# Driver.net
KiCad netlist of a schematic drawn in EAGLE
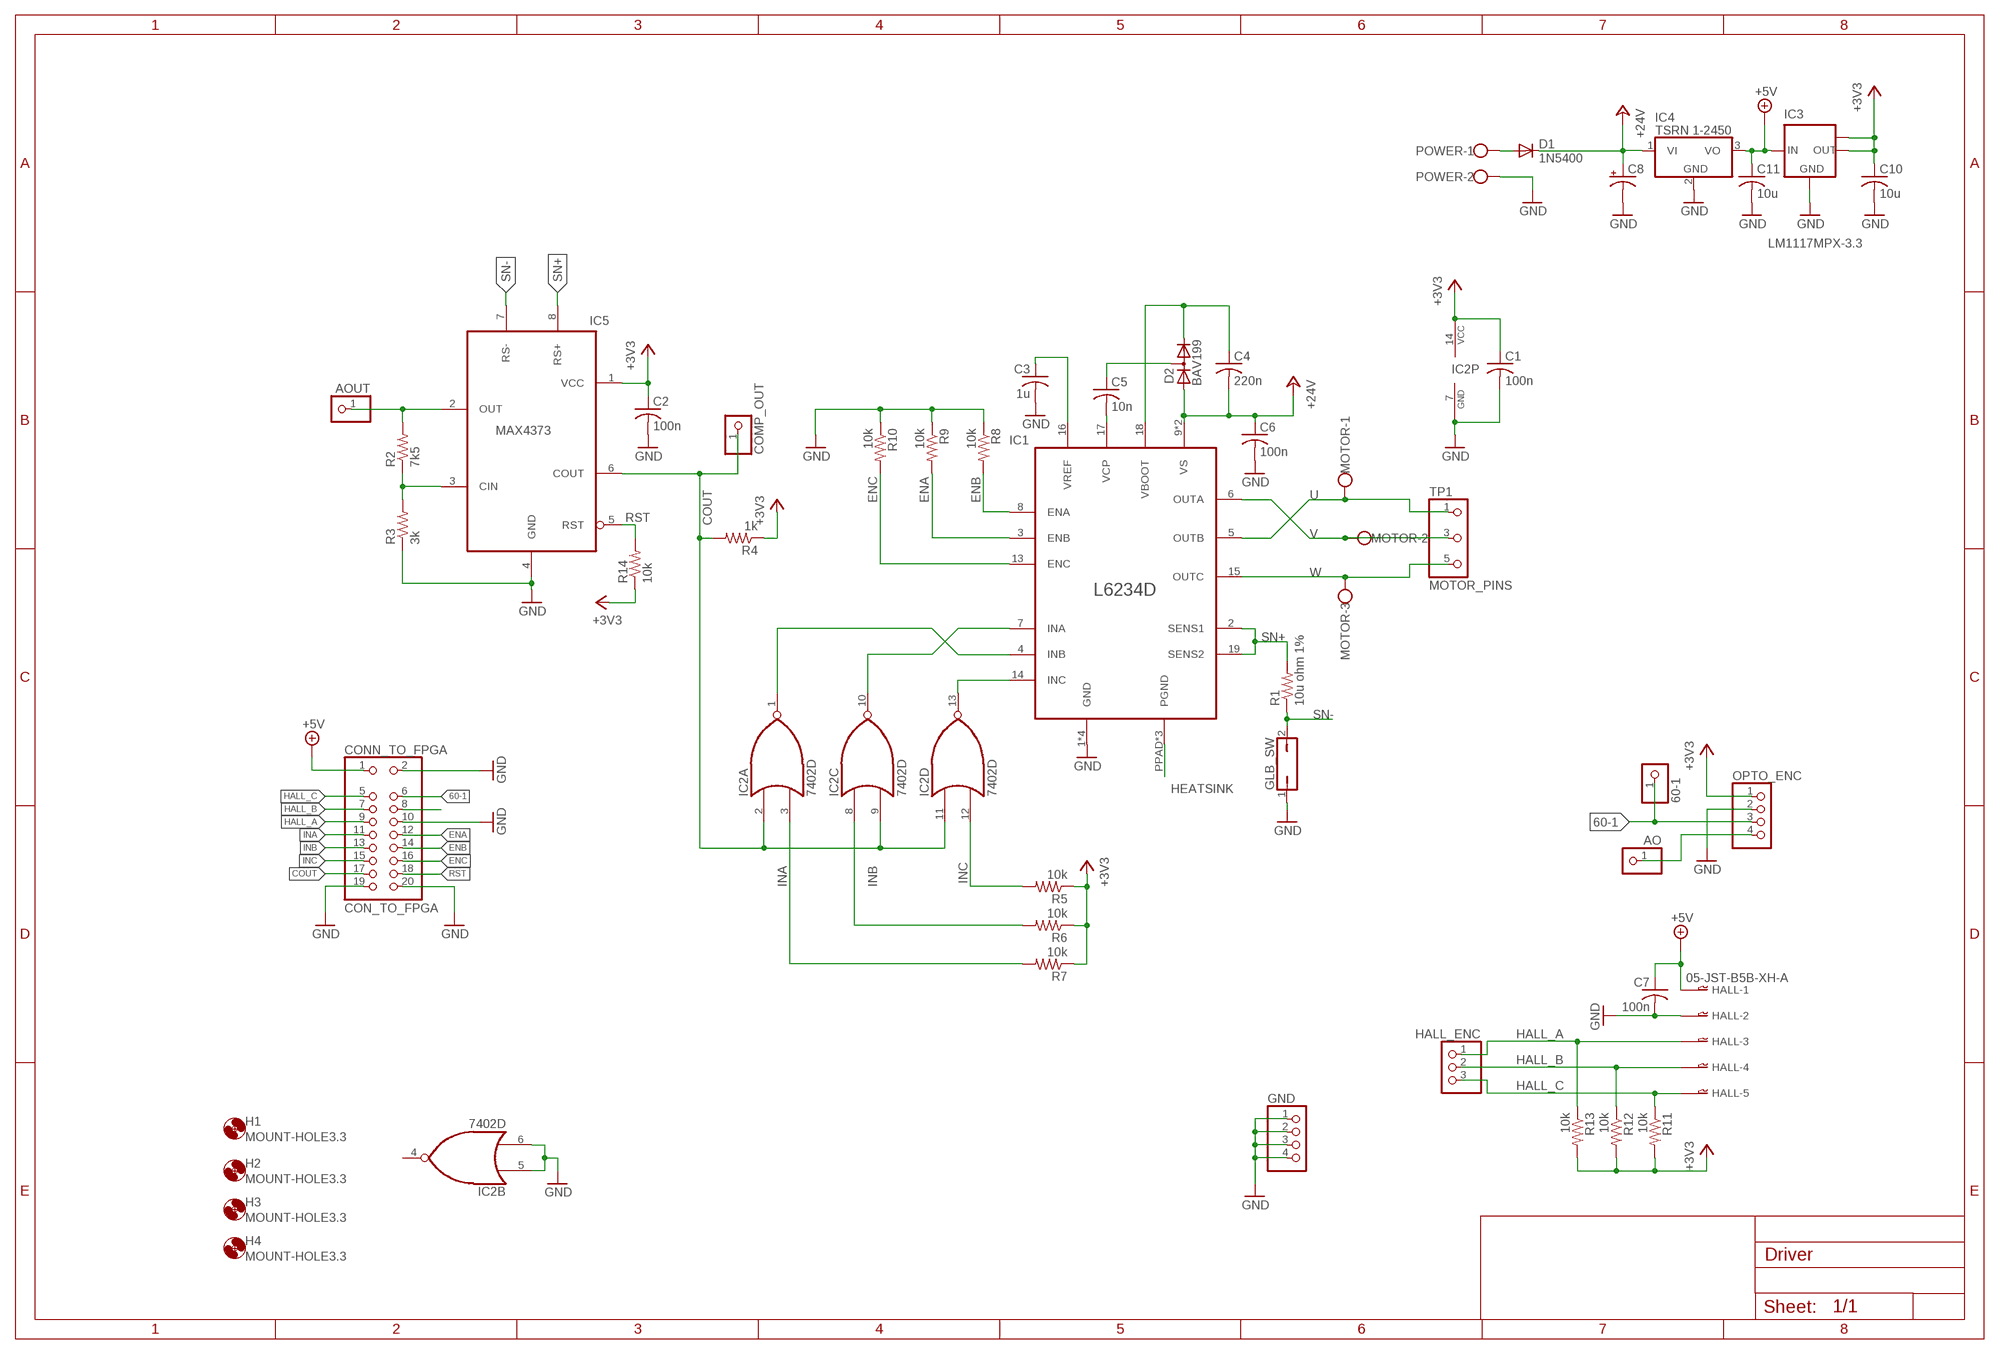
[diagram p0: schematic, sheet 1]

(export (version "E")
  (design (tool "Eeschema 10.0.6"))
  (components
    (comp (ref "60-1")
      (value "PINHD-1X1")
      (footprint "eagle-import:1X01")
      (libsource (lib "eagle-import") (part "PINHD-1X1"))
    )
    (comp (ref "AO")
      (value "PINHD-1X1")
      (footprint "eagle-import:1X01")
      (libsource (lib "eagle-import") (part "PINHD-1X1"))
    )
    (comp (ref "AOUT")
      (value "PINHD-1X1")
      (footprint "eagle-import:1X01")
      (libsource (lib "eagle-import") (part "PINHD-1X1"))
    )
    (comp (ref "C1")
      (value "100n")
      (footprint "eagle-import:C0805")
      (libsource (lib "eagle-import") (part "C-USC0805"))
    )
    (comp (ref "C2")
      (value "100n")
      (footprint "eagle-import:C0805")
      (libsource (lib "eagle-import") (part "C-USC0805"))
    )
    (comp (ref "C3")
      (value "1u")
      (footprint "eagle-import:C0805")
      (libsource (lib "eagle-import") (part "C-USC0805"))
    )
    (comp (ref "C4")
      (value "220n")
      (footprint "eagle-import:C0805")
      (libsource (lib "eagle-import") (part "C-USC0805"))
    )
    (comp (ref "C5")
      (value "10n")
      (footprint "eagle-import:C0805")
      (libsource (lib "eagle-import") (part "C-USC0805"))
    )
    (comp (ref "C6")
      (value "100n")
      (footprint "eagle-import:C0805")
      (libsource (lib "eagle-import") (part "C-USC0805"))
    )
    (comp (ref "C7")
      (value "100n")
      (footprint "eagle-import:C0805")
      (libsource (lib "eagle-import") (part "C-USC0805"))
    )
    (comp (ref "C8")
      (value "CPOL-USE5-13")
      (footprint "eagle-import:E5-13")
      (libsource (lib "eagle-import") (part "CPOL-USE5-13"))
    )
    (comp (ref "C10")
      (value "10u")
      (footprint "eagle-import:C1206K")
      (libsource (lib "eagle-import") (part "C-USC1206K"))
    )
    (comp (ref "C11")
      (value "10u")
      (footprint "eagle-import:C1206K")
      (libsource (lib "eagle-import") (part "C-USC1206K"))
    )
    (comp (ref "COMP_OUT")
      (value "PINHD-1X1")
      (footprint "eagle-import:1X01")
      (libsource (lib "eagle-import") (part "PINHD-1X1"))
    )
    (comp (ref "CONN_TO_FPGA")
      (value "CON_TO_FPGA")
      (footprint "eagle-import:2X10-2")
      (libsource (lib "eagle-import") (part "CON_TO_FPGA"))
    )
    (comp (ref "D1")
      (value "1N5400")
      (footprint "eagle-import:DO201-15")
      (libsource (lib "eagle-import") (part "1N5400"))
    )
    (comp (ref "D2")
      (value "BAV199")
      (footprint "eagle-import:SOT23")
      (libsource (lib "eagle-import") (part "BAV199"))
    )
    (comp (ref "GLB_SW")
      (value "JP1Q")
      (footprint "eagle-import:JP1")
      (libsource (lib "eagle-import") (part "JP1Q"))
    )
    (comp (ref "GND")
      (value "PINHD-1X4")
      (footprint "eagle-import:1X04")
      (libsource (lib "eagle-import") (part "PINHD-1X4"))
    )
    (comp (ref "H1")
      (value "MOUNT-HOLE3.3")
      (footprint "eagle-import:3,3")
      (libsource (lib "eagle-import") (part "MOUNT-HOLE3.3"))
    )
    (comp (ref "H2")
      (value "MOUNT-HOLE3.3")
      (footprint "eagle-import:3,3")
      (libsource (lib "eagle-import") (part "MOUNT-HOLE3.3"))
    )
    (comp (ref "H3")
      (value "MOUNT-HOLE3.3")
      (footprint "eagle-import:3,3")
      (libsource (lib "eagle-import") (part "MOUNT-HOLE3.3"))
    )
    (comp (ref "H4")
      (value "MOUNT-HOLE3.3")
      (footprint "eagle-import:3,3")
      (libsource (lib "eagle-import") (part "MOUNT-HOLE3.3"))
    )
    (comp (ref "HALL")
      (value "05-JST-B5B-XH-A")
      (footprint "eagle-import:B5B-XH")
      (libsource (lib "eagle-import") (part "05-JST-B5B-XH-A"))
    )
    (comp (ref "HALL_ENC")
      (value "PINHD-1X3")
      (footprint "eagle-import:1X03")
      (libsource (lib "eagle-import") (part "PINHD-1X3"))
    )
    (comp (ref "IC1")
      (value "L6234D")
      (footprint "eagle-import:POWER_SO20")
      (libsource (lib "eagle-import") (part "L6234D"))
    )
    (comp (ref "IC2")
      (value "7402D")
      (footprint "eagle-import:SO14")
      (libsource (lib "eagle-import") (part "7402D"))
    )
    (comp (ref "IC3")
      (value "LM1117MPX-3.3")
      (footprint "eagle-import:SOT223")
      (libsource (lib "eagle-import") (part "LM1117MPX-3.3"))
    )
    (comp (ref "IC4")
      (value "TSRN 1-2450")
      (footprint "eagle-import:TSRN-1")
      (libsource (lib "eagle-import") (part "REG"))
    )
    (comp (ref "IC5")
      (value "MAX4373")
      (footprint "eagle-import:SO-8")
      (libsource (lib "eagle-import") (part "MAX4373"))
    )
    (comp (ref "MOTOR")
      (value "W237-103")
      (footprint "eagle-import:W237-103")
      (fields (field (name "MPN") "237-103"))
      (libsource (lib "eagle-import") (part "W237-103"))
    )
    (comp (ref "OPTO_ENC")
      (value "PINHD-1X4")
      (footprint "eagle-import:1X04")
      (libsource (lib "eagle-import") (part "PINHD-1X4"))
    )
    (comp (ref "POWER")
      (value "W237-102")
      (footprint "eagle-import:W237-102")
      (fields (field (name "MPN") "237-102"))
      (libsource (lib "eagle-import") (part "W237-102"))
    )
    (comp (ref "R1")
      (value "10u ohm 1%")
      (footprint "eagle-import:R2512")
      (libsource (lib "eagle-import") (part "R-US_R2512"))
    )
    (comp (ref "R2")
      (value "7k5")
      (footprint "eagle-import:M1206")
      (libsource (lib "eagle-import") (part "R-US_M1206"))
    )
    (comp (ref "R3")
      (value "3k")
      (footprint "eagle-import:M1206")
      (libsource (lib "eagle-import") (part "R-US_M1206"))
    )
    (comp (ref "R4")
      (value "1k")
      (footprint "eagle-import:M1206")
      (libsource (lib "eagle-import") (part "R-US_M1206"))
    )
    (comp (ref "R5")
      (value "10k")
      (footprint "eagle-import:M1206")
      (libsource (lib "eagle-import") (part "R-US_M1206"))
    )
    (comp (ref "R6")
      (value "10k")
      (footprint "eagle-import:M1206")
      (libsource (lib "eagle-import") (part "R-US_M1206"))
    )
    (comp (ref "R7")
      (value "10k")
      (footprint "eagle-import:M1206")
      (libsource (lib "eagle-import") (part "R-US_M1206"))
    )
    (comp (ref "R8")
      (value "10k")
      (footprint "eagle-import:M1206")
      (libsource (lib "eagle-import") (part "R-US_M1206"))
    )
    (comp (ref "R9")
      (value "10k")
      (footprint "eagle-import:M1206")
      (libsource (lib "eagle-import") (part "R-US_M1206"))
    )
    (comp (ref "R10")
      (value "10k")
      (footprint "eagle-import:M1206")
      (libsource (lib "eagle-import") (part "R-US_M1206"))
    )
    (comp (ref "R11")
      (value "10k")
      (footprint "eagle-import:M1206")
      (libsource (lib "eagle-import") (part "R-US_M1206"))
    )
    (comp (ref "R12")
      (value "10k")
      (footprint "eagle-import:M1206")
      (libsource (lib "eagle-import") (part "R-US_M1206"))
    )
    (comp (ref "R13")
      (value "10k")
      (footprint "eagle-import:M1206")
      (libsource (lib "eagle-import") (part "R-US_M1206"))
    )
    (comp (ref "R14")
      (value "10k")
      (footprint "eagle-import:M1206")
      (libsource (lib "eagle-import") (part "R-US_M1206"))
    )
    (comp (ref "TP1")
      (value "MOTOR_PINS")
      (footprint "eagle-import:PINSX3-200")
      (libsource (lib "eagle-import") (part "MOTOR_PINS"))
    )
  )
  (nets
    (net (code "1") (name "+3V3") (class "Default")
      (node (ref "C1") (pin "1") (pinfunction "1_1") (pintype "passive"))
      (node (ref "C10") (pin "1") (pinfunction "1_1") (pintype "passive"))
      (node (ref "C2") (pin "1") (pinfunction "1_1") (pintype "passive"))
      (node (ref "IC2") (pin "14") (pinfunction "VCC_14") (pintype "power_in"))
      (node (ref "IC3") (pin "2") (pinfunction "OUT_2") (pintype "passive"))
      (node (ref "IC3") (pin "TAB") (pinfunction "OUT1_TAB") (pintype "passive"))
      (node (ref "IC5") (pin "1") (pinfunction "VCC_1") (pintype "power_in"))
      (node (ref "OPTO_ENC") (pin "1") (pinfunction "1_1") (pintype "passive"))
      (node (ref "R11") (pin "2") (pinfunction "2_2") (pintype "passive"))
      (node (ref "R12") (pin "2") (pinfunction "2_2") (pintype "passive"))
      (node (ref "R13") (pin "2") (pinfunction "2_2") (pintype "passive"))
      (node (ref "R14") (pin "1") (pinfunction "1_1") (pintype "passive"))
      (node (ref "R4") (pin "1") (pinfunction "1_1") (pintype "passive"))
      (node (ref "R5") (pin "1") (pinfunction "1_1") (pintype "passive"))
      (node (ref "R6") (pin "1") (pinfunction "1_1") (pintype "passive"))
      (node (ref "R7") (pin "1") (pinfunction "1_1") (pintype "passive"))
    )
    (net (code "2") (name "+5V") (class "Default")
      (node (ref "C11") (pin "1") (pinfunction "1_1") (pintype "passive"))
      (node (ref "C7") (pin "1") (pinfunction "1_1") (pintype "passive"))
      (node (ref "CONN_TO_FPGA") (pin "1") (pinfunction "1_1") (pintype "passive"))
      (node (ref "HALL") (pin "P$1") (pinfunction "1_P$1") (pintype "passive"))
      (node (ref "IC3") (pin "3") (pinfunction "IN_3") (pintype "input"))
      (node (ref "IC4") (pin "3") (pinfunction "VO_3") (pintype "passive"))
    )
    (net (code "3") (name "+24V") (class "Default")
      (node (ref "C4") (pin "2") (pinfunction "2_2") (pintype "passive"))
      (node (ref "C6") (pin "1") (pinfunction "1_1") (pintype "passive"))
      (node (ref "C8") (pin "+") (pinfunction "+_+") (pintype "passive"))
      (node (ref "D1") (pin "C") (pinfunction "C_C") (pintype "passive"))
      (node (ref "D2") (pin "1") (pinfunction "A_1") (pintype "passive"))
      (node (ref "IC1") (pin "12") (pinfunction "VS_12") (pintype "power_in"))
      (node (ref "IC1") (pin "9") (pinfunction "VS_9") (pintype "power_in"))
      (node (ref "IC4") (pin "1") (pinfunction "VI_1") (pintype "input"))
    )
    (net (code "4") (name "/HEATSINK") (class "Default")
      (node (ref "IC1") (pin "PPAD") (pinfunction "PGND_PPAD") (pintype "power_in"))
      (node (ref "IC1") (pin "PPAD1") (pinfunction "PGND_PPAD1") (pintype "power_in"))
      (node (ref "IC1") (pin "PPAD2") (pinfunction "PGND_PPAD2") (pintype "power_in"))
    )
    (net (code "5") (name "/U") (class "Default")
      (node (ref "IC1") (pin "5") (pinfunction "OUTB_5") (pintype "output"))
      (node (ref "MOTOR") (pin "1") (pinfunction "KL_1") (pintype "passive"))
      (node (ref "TP1") (pin "1") (pinfunction "1_1") (pintype "passive"))
    )
    (net (code "6") (name "/V") (class "Default")
      (node (ref "IC1") (pin "6") (pinfunction "OUTA_6") (pintype "output"))
      (node (ref "MOTOR") (pin "2") (pinfunction "KL_2") (pintype "passive"))
      (node (ref "TP1") (pin "3") (pinfunction "3_3") (pintype "passive"))
    )
    (net (code "7") (name "/W") (class "Default")
      (node (ref "IC1") (pin "15") (pinfunction "OUTC_15") (pintype "output"))
      (node (ref "MOTOR") (pin "3") (pinfunction "KL_3") (pintype "passive"))
      (node (ref "TP1") (pin "5") (pinfunction "5_5") (pintype "passive"))
    )
    (net (code "8") (name "60-1") (class "Default")
      (node (ref "60-1") (pin "1") (pinfunction "1_1") (pintype "passive"))
      (node (ref "CONN_TO_FPGA") (pin "6") (pinfunction "6_6") (pintype "passive"))
      (node (ref "OPTO_ENC") (pin "3") (pinfunction "3_3") (pintype "passive"))
    )
    (net (code "9") (name "COUT") (class "Default")
      (node (ref "COMP_OUT") (pin "1") (pinfunction "1_1") (pintype "passive"))
      (node (ref "CONN_TO_FPGA") (pin "17") (pinfunction "17_17") (pintype "passive"))
      (node (ref "IC2") (pin "11") (pinfunction "I0_11") (pintype "input"))
      (node (ref "IC2") (pin "2") (pinfunction "I0_2") (pintype "input"))
      (node (ref "IC2") (pin "9") (pinfunction "I1_9") (pintype "input"))
      (node (ref "IC5") (pin "6") (pinfunction "COUT_6") (pintype "output"))
      (node (ref "R4") (pin "2") (pinfunction "2_2") (pintype "passive"))
    )
    (net (code "10") (name "ENA") (class "Default")
      (node (ref "CONN_TO_FPGA") (pin "12") (pinfunction "12_12") (pintype "passive"))
      (node (ref "IC1") (pin "3") (pinfunction "ENB_3") (pintype "input"))
      (node (ref "R9") (pin "2") (pinfunction "2_2") (pintype "passive"))
    )
    (net (code "11") (name "ENB") (class "Default")
      (node (ref "CONN_TO_FPGA") (pin "14") (pinfunction "14_14") (pintype "passive"))
      (node (ref "IC1") (pin "8") (pinfunction "ENA_8") (pintype "input"))
      (node (ref "R8") (pin "2") (pinfunction "2_2") (pintype "passive"))
    )
    (net (code "12") (name "ENC") (class "Default")
      (node (ref "CONN_TO_FPGA") (pin "16") (pinfunction "16_16") (pintype "passive"))
      (node (ref "IC1") (pin "13") (pinfunction "ENC_13") (pintype "input"))
      (node (ref "R10") (pin "2") (pinfunction "2_2") (pintype "passive"))
    )
    (net (code "13") (name "GND") (class "Default")
      (node (ref "C1") (pin "2") (pinfunction "2_2") (pintype "passive"))
      (node (ref "C10") (pin "2") (pinfunction "2_2") (pintype "passive"))
      (node (ref "C11") (pin "2") (pinfunction "2_2") (pintype "passive"))
      (node (ref "C2") (pin "2") (pinfunction "2_2") (pintype "passive"))
      (node (ref "C3") (pin "2") (pinfunction "2_2") (pintype "passive"))
      (node (ref "C6") (pin "2") (pinfunction "2_2") (pintype "passive"))
      (node (ref "C7") (pin "2") (pinfunction "2_2") (pintype "passive"))
      (node (ref "C8") (pin "-") (pinfunction "-_-") (pintype "passive"))
      (node (ref "CONN_TO_FPGA") (pin "10") (pinfunction "10_10") (pintype "passive"))
      (node (ref "CONN_TO_FPGA") (pin "19") (pinfunction "19_19") (pintype "passive"))
      (node (ref "CONN_TO_FPGA") (pin "2") (pinfunction "2_2") (pintype "passive"))
      (node (ref "CONN_TO_FPGA") (pin "20") (pinfunction "20_20") (pintype "passive"))
      (node (ref "GLB_SW") (pin "1") (pinfunction "1_1") (pintype "passive"))
      (node (ref "GND") (pin "1") (pinfunction "1_1") (pintype "passive"))
      (node (ref "GND") (pin "2") (pinfunction "2_2") (pintype "passive"))
      (node (ref "GND") (pin "3") (pinfunction "3_3") (pintype "passive"))
      (node (ref "GND") (pin "4") (pinfunction "4_4") (pintype "passive"))
      (node (ref "HALL") (pin "P$2") (pinfunction "1_P$2") (pintype "passive"))
      (node (ref "IC1") (pin "1") (pinfunction "GND_1") (pintype "power_in"))
      (node (ref "IC1") (pin "10") (pinfunction "GND_10") (pintype "power_in"))
      (node (ref "IC1") (pin "11") (pinfunction "GND_11") (pintype "power_in"))
      (node (ref "IC1") (pin "20") (pinfunction "GND_20") (pintype "power_in"))
      (node (ref "IC2") (pin "5") (pinfunction "I0_5") (pintype "input"))
      (node (ref "IC2") (pin "6") (pinfunction "I1_6") (pintype "input"))
      (node (ref "IC2") (pin "7") (pinfunction "GND_7") (pintype "power_in"))
      (node (ref "IC3") (pin "1") (pinfunction "GND_1") (pintype "input"))
      (node (ref "IC4") (pin "2") (pinfunction "GND_2") (pintype "passive"))
      (node (ref "IC5") (pin "4") (pinfunction "GND_4") (pintype "power_in"))
      (node (ref "OPTO_ENC") (pin "2") (pinfunction "2_2") (pintype "passive"))
      (node (ref "POWER") (pin "2") (pinfunction "KL_2") (pintype "passive"))
      (node (ref "R10") (pin "1") (pinfunction "1_1") (pintype "passive"))
      (node (ref "R3") (pin "1") (pinfunction "1_1") (pintype "passive"))
      (node (ref "R8") (pin "1") (pinfunction "1_1") (pintype "passive"))
      (node (ref "R9") (pin "1") (pinfunction "1_1") (pintype "passive"))
    )
    (net (code "14") (name "HALL_A") (class "Default")
      (node (ref "CONN_TO_FPGA") (pin "9") (pinfunction "9_9") (pintype "passive"))
      (node (ref "HALL") (pin "P$3") (pinfunction "1_P$3") (pintype "passive"))
      (node (ref "HALL_ENC") (pin "1") (pinfunction "1_1") (pintype "passive"))
      (node (ref "R13") (pin "1") (pinfunction "1_1") (pintype "passive"))
    )
    (net (code "15") (name "HALL_B") (class "Default")
      (node (ref "CONN_TO_FPGA") (pin "7") (pinfunction "7_7") (pintype "passive"))
      (node (ref "HALL") (pin "P$4") (pinfunction "1_P$4") (pintype "passive"))
      (node (ref "HALL_ENC") (pin "2") (pinfunction "2_2") (pintype "passive"))
      (node (ref "R12") (pin "1") (pinfunction "1_1") (pintype "passive"))
    )
    (net (code "16") (name "HALL_C") (class "Default")
      (node (ref "CONN_TO_FPGA") (pin "5") (pinfunction "5_5") (pintype "passive"))
      (node (ref "HALL") (pin "P$5") (pinfunction "1_P$5") (pintype "passive"))
      (node (ref "HALL_ENC") (pin "3") (pinfunction "3_3") (pintype "passive"))
      (node (ref "R11") (pin "1") (pinfunction "1_1") (pintype "passive"))
    )
    (net (code "17") (name "INA") (class "Default")
      (node (ref "CONN_TO_FPGA") (pin "11") (pinfunction "11_11") (pintype "passive"))
      (node (ref "IC2") (pin "3") (pinfunction "I1_3") (pintype "input"))
      (node (ref "R7") (pin "2") (pinfunction "2_2") (pintype "passive"))
    )
    (net (code "18") (name "INB") (class "Default")
      (node (ref "CONN_TO_FPGA") (pin "13") (pinfunction "13_13") (pintype "passive"))
      (node (ref "IC2") (pin "8") (pinfunction "I0_8") (pintype "input"))
      (node (ref "R6") (pin "2") (pinfunction "2_2") (pintype "passive"))
    )
    (net (code "19") (name "INC") (class "Default")
      (node (ref "CONN_TO_FPGA") (pin "15") (pinfunction "15_15") (pintype "passive"))
      (node (ref "IC2") (pin "12") (pinfunction "I1_12") (pintype "input"))
      (node (ref "R5") (pin "2") (pinfunction "2_2") (pintype "passive"))
    )
    (net (code "20") (name "Net-(AO-Pad1)") (class "Default")
      (node (ref "AO") (pin "1") (pinfunction "1_1") (pintype "passive"))
      (node (ref "OPTO_ENC") (pin "4") (pinfunction "4_4") (pintype "passive"))
    )
    (net (code "21") (name "Net-(D2-AC)") (class "Default")
      (node (ref "C5") (pin "1") (pinfunction "1_1") (pintype "passive"))
      (node (ref "D2") (pin "3") (pinfunction "AC_3") (pintype "passive"))
    )
    (net (code "22") (name "Net-(D2-C)") (class "Default")
      (node (ref "C4") (pin "1") (pinfunction "1_1") (pintype "passive"))
      (node (ref "D2") (pin "2") (pinfunction "C_2") (pintype "passive"))
      (node (ref "IC1") (pin "18") (pinfunction "VBOOT_18") (pintype "bidirectional"))
    )
    (net (code "23") (name "Net-(IC1-INA)") (class "Default")
      (node (ref "IC1") (pin "7") (pinfunction "INA_7") (pintype "input"))
      (node (ref "IC2") (pin "10") (pinfunction "O_10") (pintype "output"))
    )
    (net (code "24") (name "Net-(IC1-INB)") (class "Default")
      (node (ref "IC1") (pin "4") (pinfunction "INB_4") (pintype "input"))
      (node (ref "IC2") (pin "1") (pinfunction "O_1") (pintype "output"))
    )
    (net (code "25") (name "Net-(IC1-INC)") (class "Default")
      (node (ref "IC1") (pin "14") (pinfunction "INC_14") (pintype "input"))
      (node (ref "IC2") (pin "13") (pinfunction "O_13") (pintype "output"))
    )
    (net (code "26") (name "Net-(IC1-VCP)") (class "Default")
      (node (ref "C5") (pin "2") (pinfunction "2_2") (pintype "passive"))
      (node (ref "IC1") (pin "17") (pinfunction "VCP_17") (pintype "bidirectional"))
    )
    (net (code "27") (name "Net-(IC1-VREF)") (class "Default")
      (node (ref "C3") (pin "1") (pinfunction "1_1") (pintype "passive"))
      (node (ref "IC1") (pin "16") (pinfunction "VREF_16") (pintype "bidirectional"))
    )
    (net (code "28") (name "Net-(IC5-CIN)") (class "Default")
      (node (ref "IC5") (pin "3") (pinfunction "CIN_3") (pintype "input"))
      (node (ref "R2") (pin "1") (pinfunction "1_1") (pintype "passive"))
      (node (ref "R3") (pin "2") (pinfunction "2_2") (pintype "passive"))
    )
    (net (code "29") (name "Net-(IC5-OUT)") (class "Default")
      (node (ref "AOUT") (pin "1") (pinfunction "1_1") (pintype "passive"))
      (node (ref "IC5") (pin "2") (pinfunction "OUT_2") (pintype "output"))
      (node (ref "R2") (pin "2") (pinfunction "2_2") (pintype "passive"))
    )
    (net (code "30") (name "Net-(POWERA-KL)") (class "Default")
      (node (ref "D1") (pin "A") (pinfunction "A_A") (pintype "passive"))
      (node (ref "POWER") (pin "1") (pinfunction "KL_1") (pintype "passive"))
    )
    (net (code "31") (name "RST") (class "Default")
      (node (ref "CONN_TO_FPGA") (pin "18") (pinfunction "18_18") (pintype "passive"))
      (node (ref "IC5") (pin "5") (pinfunction "RST_5") (pintype "input"))
      (node (ref "R14") (pin "2") (pinfunction "2_2") (pintype "passive"))
    )
    (net (code "32") (name "SN+") (class "Default")
      (node (ref "IC1") (pin "19") (pinfunction "SENS2_19") (pintype "output"))
      (node (ref "IC1") (pin "2") (pinfunction "SENS1_2") (pintype "output"))
      (node (ref "IC5") (pin "8") (pinfunction "RS+_8") (pintype "bidirectional"))
      (node (ref "R1") (pin "2") (pinfunction "2_2") (pintype "passive"))
    )
    (net (code "33") (name "SN-") (class "Default")
      (node (ref "GLB_SW") (pin "2") (pinfunction "2_2") (pintype "passive"))
      (node (ref "IC5") (pin "7") (pinfunction "RS-_7") (pintype "bidirectional"))
      (node (ref "R1") (pin "1") (pinfunction "1_1") (pintype "passive"))
    )
    (net (code "34") (name "unconnected-(CONN_TO_FPGA-Pad8)") (class "Default")
      (node (ref "CONN_TO_FPGA") (pin "8") (pinfunction "8_8") (pintype "passive"))
    )
    (net (code "35") (name "unconnected-(IC2B-O-Pad4)") (class "Default")
      (node (ref "IC2") (pin "4") (pinfunction "O_4") (pintype "output"))
    )
  )
)
